# Frost5000Beta_Sch.net
KiCad netlist of a schematic drawn in Altium Designer
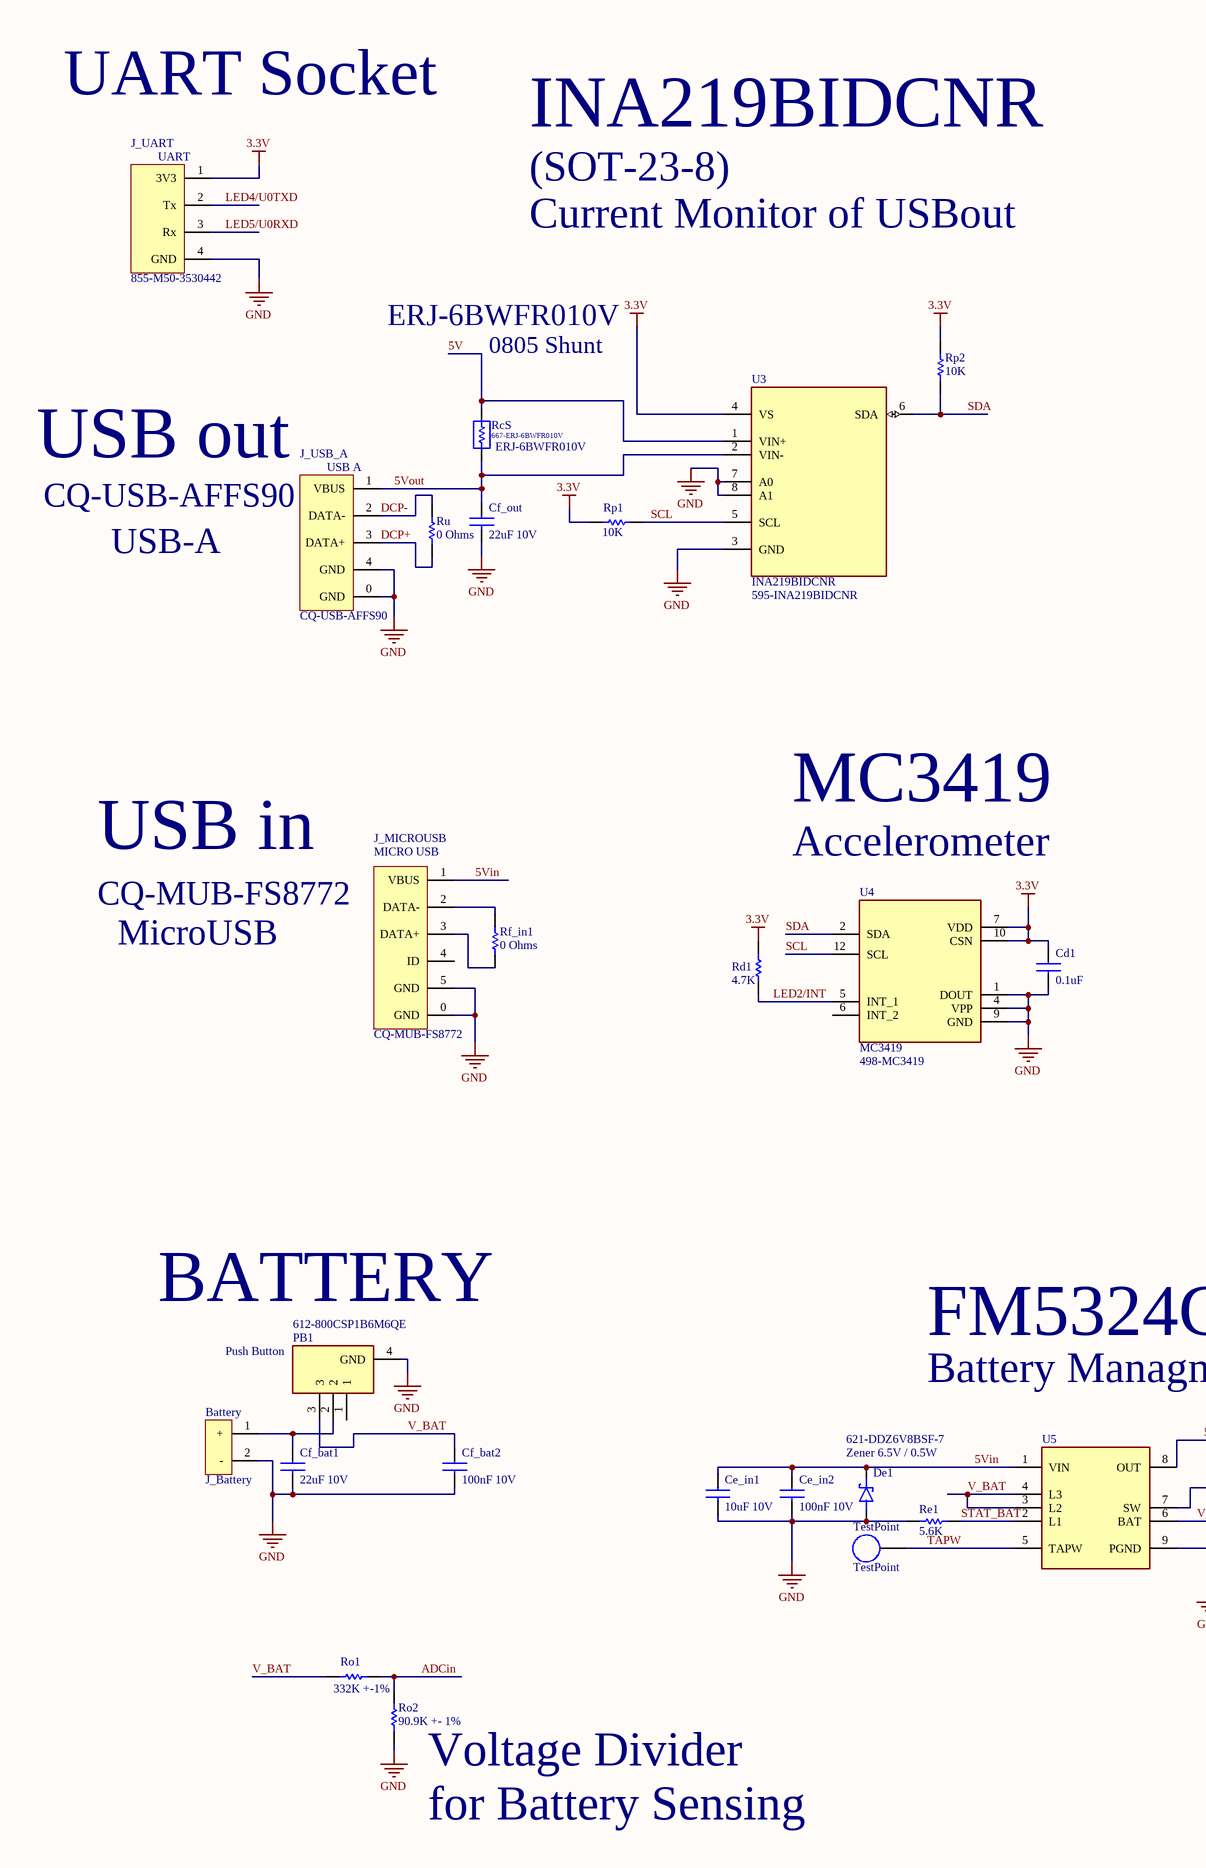
[diagram p0: Frost5000Beta_Sch.SchDoc, left]
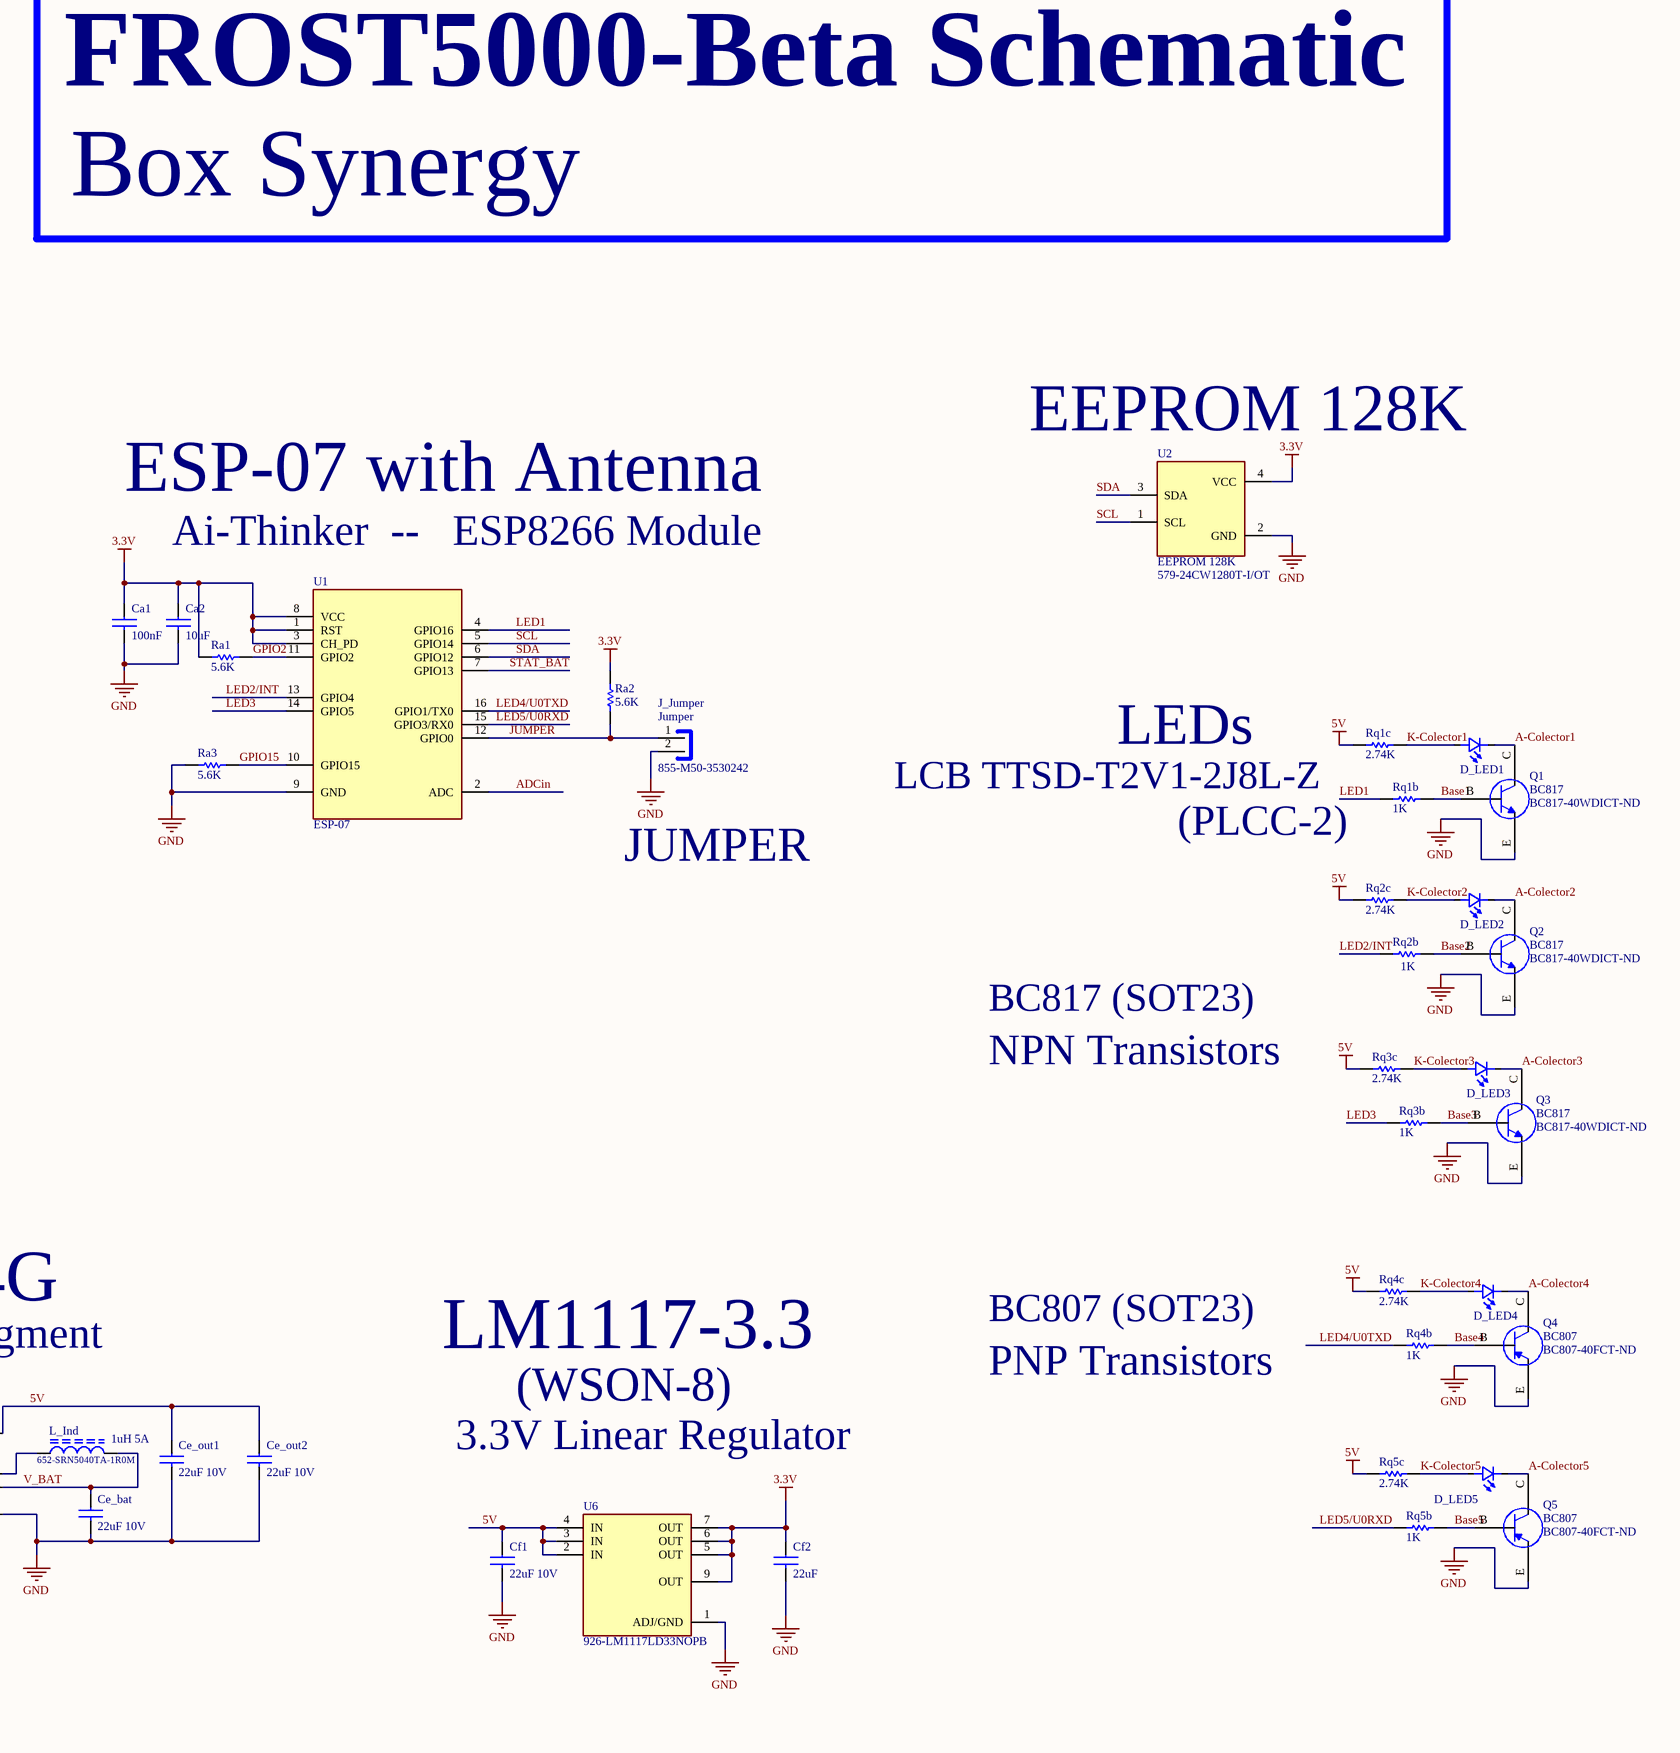
[diagram p1: Frost5000Beta_Sch.SchDoc, right]

(export (version "E")
  (design (tool "Eeschema 10.0.6"))
  (components
    (comp (ref "Ca1")
      (value "100nF")
      (footprint "CAP_0603")
      (description "Capac Ceramic SMD 0603")
      (libsource (lib "Frost5000Beta_LIB_Pasivos_Sch") (part "Cap_0603_Ceramic"))
    )
    (comp (ref "Ca2")
      (value "10uF")
      (footprint "CAP_1206")
      (description "Capac Ceramic SMD")
      (libsource (lib "Frost5000Beta_LIB_Pasivos_Sch") (part "Cap_1206_Ceramic"))
    )
    (comp (ref "Cd1")
      (value "0.1uF")
      (footprint "CAP_0603")
      (description "Capac Ceramic SMD 0603")
      (libsource (lib "Frost5000Beta_LIB_Pasivos_Sch") (part "Cap_0603_Ceramic"))
    )
    (comp (ref "Ce_bat")
      (value "22uF 10V")
      (footprint "CAP_1206")
      (description "Capac Ceramic SMD")
      (libsource (lib "Frost5000Beta_LIB_Pasivos_Sch") (part "Cap_1206_Ceramic"))
    )
    (comp (ref "Ce_in1")
      (value "10uF 10V")
      (footprint "CAP_1206")
      (description "Capac Ceramic SMD")
      (libsource (lib "Frost5000Beta_LIB_Pasivos_Sch") (part "Cap_1206_Ceramic"))
    )
    (comp (ref "Ce_in2")
      (value "100nF 10V")
      (footprint "CAP_0603")
      (description "Capac Ceramic SMD 0603")
      (libsource (lib "Frost5000Beta_LIB_Pasivos_Sch") (part "Cap_0603_Ceramic"))
    )
    (comp (ref "Ce_out1")
      (value "22uF 10V")
      (footprint "CAP_1210")
      (description "Capac Ceramic SMD 1210")
      (libsource (lib "Frost5000Beta_LIB_Pasivos_Sch") (part "Cap_1210_Ceramic"))
    )
    (comp (ref "Ce_out2")
      (value "22uF 10V")
      (footprint "CAP_1206")
      (description "Capac Ceramic SMD")
      (libsource (lib "Frost5000Beta_LIB_Pasivos_Sch") (part "Cap_1206_Ceramic"))
    )
    (comp (ref "Cf1")
      (value "22uF 10V")
      (footprint "CAP_0603")
      (description "Capac Ceramic SMD 0603")
      (libsource (lib "Frost5000Beta_LIB_Pasivos_Sch") (part "Cap_0603_Ceramic"))
    )
    (comp (ref "Cf2")
      (value "22uF")
      (footprint "CAP_0603")
      (description "Capac Ceramic SMD 0603")
      (libsource (lib "Frost5000Beta_LIB_Pasivos_Sch") (part "Cap_0603_Ceramic"))
    )
    (comp (ref "Cf_bat1")
      (value "22uF 10V")
      (footprint "CAP_1206")
      (description "Capac Ceramic SMD")
      (libsource (lib "Frost5000Beta_LIB_Pasivos_Sch") (part "Cap_1206_Ceramic"))
    )
    (comp (ref "Cf_bat2")
      (value "100nF 10V")
      (footprint "CAP_0603")
      (description "Capac Ceramic SMD 0603")
      (libsource (lib "Frost5000Beta_LIB_Pasivos_Sch") (part "Cap_0603_Ceramic"))
    )
    (comp (ref "Cf_out")
      (value "22uF 10V")
      (footprint "CAP_1210")
      (description "Capac Ceramic SMD 1210")
      (libsource (lib "Frost5000Beta_LIB_Pasivos_Sch") (part "Cap_1210_Ceramic"))
    )
    (comp (ref "De1")
      (value "Zener 6.5V / 0.5W")
      (footprint "Zener-SOD323F")
      (fields
        (field (name "MF") "Littelfuse")
        (field (name "MP") "SMF5.0AT1G")
        (field (name "SUPPLIER PART NUMBER 1") "621-DDZ6V8BSF-7")
      )
      (libsource (lib "Frost5000Beta_LIB_Otros_Sch") (part "Zener"))
    )
    (comp (ref "D_LED1")
      (value "LCB TTSD-T2V1-2J8L-Z")
      (footprint "LED_PLCC-2")
      (description "Blue LED PLCC-2")
      (fields (field (name "MF") "Broadcom Limited") (field (name "MP") "HSMW-C191"))
      (libsource (lib "Frost5000Beta_LIB_Otros_Sch") (part "LCB_TTSD"))
    )
    (comp (ref "D_LED2")
      (value "LCB TTSD-T2V1-2J8L-Z")
      (footprint "LED_PLCC-2")
      (description "Blue LED PLCC-2")
      (fields (field (name "MF") "Broadcom Limited") (field (name "MP") "HSMW-C191"))
      (libsource (lib "Frost5000Beta_LIB_Otros_Sch") (part "LCB_TTSD"))
    )
    (comp (ref "D_LED3")
      (value "LCB TTSD-T2V1-2J8L-Z")
      (footprint "LED_PLCC-2")
      (description "Blue LED PLCC-2")
      (fields (field (name "MF") "Broadcom Limited") (field (name "MP") "HSMW-C191"))
      (libsource (lib "Frost5000Beta_LIB_Otros_Sch") (part "LCB_TTSD"))
    )
    (comp (ref "D_LED4")
      (value "LCB TTSD-T2V1-2J8L-Z")
      (footprint "LED_PLCC-2")
      (description "Blue LED PLCC-2")
      (fields (field (name "MF") "Broadcom Limited") (field (name "MP") "HSMW-C191"))
      (libsource (lib "Frost5000Beta_LIB_Otros_Sch") (part "LCB_TTSD"))
    )
    (comp (ref "D_LED5")
      (value "LCB TTSD-T2V1-2J8L-Z")
      (footprint "LED_PLCC-2")
      (description "Blue LED PLCC-2")
      (fields (field (name "MF") "Broadcom Limited") (field (name "MP") "HSMW-C191"))
      (libsource (lib "Frost5000Beta_LIB_Otros_Sch") (part "LCB_TTSD"))
    )
    (comp (ref "J_Battery")
      (value "Connx2_Battery")
      (footprint "Battery")
      (description "NO SOCKET")
      (libsource (lib "Frost5000Beta_LIB_Conectores_Sch") (part "Connx2_Battery"))
    )
    (comp (ref "J_Jumper")
      (value "M50-3530242")
      (footprint "JUMPER-1.27 mm")
      (description "1.27mm Pin Header 2x1")
      (fields (field (name "SUPPLIER PART NUMBER 1") "855-M50-3530242"))
      (libsource (lib "Summits7Beta_LIB_Conectores_Sch") (part "Jumper"))
    )
    (comp (ref "J_MICROUSB")
      (value "CQ-MUB-FS8772")
      (footprint "MICRO USB")
      (description "MicroUSB B-type Socket")
      (libsource (lib "Frost5000Beta_LIB_Conectores_Sch") (part "MicroUSB"))
    )
    (comp (ref "J_UART")
      (value "M50-3530442")
      (footprint "UART-1.27mm")
      (description "1.27mm Pin Header 4x1")
      (fields (field (name "SUPPLIER PART NUMBER 1") "855-M50-3530442"))
      (libsource (lib "Summits7Beta_LIB_Conectores_Sch") (part "Connx4_UART"))
    )
    (comp (ref "J_USB_A")
      (value "CQ-USB-AFFS90")
      (footprint "USB-A__IPX8")
      (description "USB-A Socket")
      (libsource (lib "Frost5000Beta_LIB_Conectores_Sch") (part "USB-A 5V"))
    )
    (comp (ref "L_Ind")
      (value "1uH 5A")
      (footprint "Inductor_SRN5040")
      (description "Inductor_SRN5040")
      (fields (field (name "MF") "Vishay Dale") (field (name "SUPPLIER PART NUMBER 1") "652-SRN5040TA-1R0M"))
      (libsource (lib "Frost5000Beta_LIB_Pasivos_Sch") (part "Ind_SRN5040"))
    )
    (comp (ref "PB1")
      (value "Push Button")
      (footprint "800C Switch")
      (description "Push Button 800C")
      (fields (field (name "SUPPLIER PART NUMBER 1") "612-800CSP1B6M6QE"))
      (libsource (lib "Frost5000Beta_LIB_Otros_Sch") (part "800C"))
    )
    (comp (ref "Q1")
      (value "BC817")
      (footprint "Transistor_SOT23-3")
      (description "Transistor NPN")
      (fields (field (name "SUPPLIER PART NUMBER 1") "BC817-40WDICT-ND"))
      (libsource (lib "Frost5000Beta_LIB_Integrados_Sch") (part "BC817"))
    )
    (comp (ref "Q2")
      (value "BC817")
      (footprint "Transistor_SOT23-3")
      (description "Transistor NPN")
      (fields (field (name "SUPPLIER PART NUMBER 1") "BC817-40WDICT-ND"))
      (libsource (lib "Frost5000Beta_LIB_Integrados_Sch") (part "BC817"))
    )
    (comp (ref "Q3")
      (value "BC817")
      (footprint "Transistor_SOT23-3")
      (description "Transistor NPN")
      (fields (field (name "SUPPLIER PART NUMBER 1") "BC817-40WDICT-ND"))
      (libsource (lib "Frost5000Beta_LIB_Integrados_Sch") (part "BC817"))
    )
    (comp (ref "Q4")
      (value "BC807")
      (footprint "Transistor_SOT23-3")
      (description "Transistor PNP")
      (fields (field (name "SUPPLIER PART NUMBER 1") "BC807-40FCT-ND"))
      (libsource (lib "Frost5000Beta_LIB_Integrados_Sch") (part "BC807"))
    )
    (comp (ref "Q5")
      (value "BC807")
      (footprint "Transistor_SOT23-3")
      (description "Transistor PNP")
      (fields (field (name "SUPPLIER PART NUMBER 1") "BC807-40FCT-ND"))
      (libsource (lib "Frost5000Beta_LIB_Integrados_Sch") (part "BC807"))
    )
    (comp (ref "Ra1")
      (value "5.6K")
      (footprint "RES_0603")
      (description "Resistor SMD")
      (fields (field (name "PUBLISHER") "Altium Limited"))
      (libsource (lib "Frost5000Beta_LIB_Pasivos_Sch") (part "Res_0603"))
    )
    (comp (ref "Ra2")
      (value "5.6K")
      (footprint "RES_0603")
      (description "Resistor SMD")
      (fields (field (name "PUBLISHER") "Altium Limited"))
      (libsource (lib "Frost5000Beta_LIB_Pasivos_Sch") (part "Res_0603"))
    )
    (comp (ref "Ra3")
      (value "5.6K")
      (footprint "RES_0603")
      (description "Resistor SMD")
      (fields (field (name "PUBLISHER") "Altium Limited"))
      (libsource (lib "Frost5000Beta_LIB_Pasivos_Sch") (part "Res_0603"))
    )
    (comp (ref "RcS")
      (value "ERJ-6BWFR010V")
      (footprint "RES-SHUNT-0805")
      (description "Shunt 0.01 Ohm 0.5W 1% SMD Resistor")
      (fields
        (field (name "SUPPLIER PART NUMBER 1") "667-ERJ-6BWFR010V")
        (field (name "PUBLISHER") "Altium Limited")
      )
      (libsource (lib "Frost5000Beta_LIB_Pasivos_Sch") (part "Shunt_0805"))
    )
    (comp (ref "Rd1")
      (value "4.7K")
      (footprint "RES_0603")
      (description "Resistor SMD")
      (fields (field (name "PUBLISHER") "Altium Limited"))
      (libsource (lib "Frost5000Beta_LIB_Pasivos_Sch") (part "Res_0603"))
    )
    (comp (ref "Re1")
      (value "5.6K")
      (footprint "RES_0603")
      (description "Resistor SMD")
      (fields (field (name "PUBLISHER") "Altium Limited"))
      (libsource (lib "Frost5000Beta_LIB_Pasivos_Sch") (part "Res_0603"))
    )
    (comp (ref "Rf_in1")
      (value "0 Ohms")
      (footprint "RES_0603")
      (description "Resistor SMD")
      (fields (field (name "PUBLISHER") "Altium Limited"))
      (libsource (lib "Frost5000Beta_LIB_Pasivos_Sch") (part "Res_0603"))
    )
    (comp (ref "Ro1")
      (value "332K +-1%")
      (footprint "RES_0603")
      (description "Resistor SMD")
      (fields (field (name "PUBLISHER") "Altium Limited"))
      (libsource (lib "Frost5000Beta_LIB_Pasivos_Sch") (part "Res_0603"))
    )
    (comp (ref "Ro2")
      (value "90.9K +- 1%")
      (footprint "RES_0603")
      (description "Resistor SMD")
      (fields (field (name "PUBLISHER") "Altium Limited"))
      (libsource (lib "Frost5000Beta_LIB_Pasivos_Sch") (part "Res_0603"))
    )
    (comp (ref "Rp1")
      (value "10K")
      (footprint "RES_0603")
      (description "Resistor SMD")
      (fields (field (name "PUBLISHER") "Altium Limited"))
      (libsource (lib "Frost5000Beta_LIB_Pasivos_Sch") (part "Res_0603"))
    )
    (comp (ref "Rp2")
      (value "10K")
      (footprint "RES_0603")
      (description "Resistor SMD")
      (fields (field (name "PUBLISHER") "Altium Limited"))
      (libsource (lib "Frost5000Beta_LIB_Pasivos_Sch") (part "Res_0603"))
    )
    (comp (ref "Rq1b")
      (value "1K")
      (footprint "RES_0603")
      (description "Resistor SMD")
      (fields (field (name "PUBLISHER") "Altium Limited"))
      (libsource (lib "Frost5000Beta_LIB_Pasivos_Sch") (part "Res_0603"))
    )
    (comp (ref "Rq1c")
      (value "2.74K")
      (footprint "RES_0603")
      (description "Resistor SMD")
      (fields (field (name "PUBLISHER") "Altium Limited"))
      (libsource (lib "Frost5000Beta_LIB_Pasivos_Sch") (part "Res_0603"))
    )
    (comp (ref "Rq2b")
      (value "1K")
      (footprint "RES_0603")
      (description "Resistor SMD")
      (fields (field (name "PUBLISHER") "Altium Limited"))
      (libsource (lib "Frost5000Beta_LIB_Pasivos_Sch") (part "Res_0603"))
    )
    (comp (ref "Rq2c")
      (value "2.74K")
      (footprint "RES_0603")
      (description "Resistor SMD")
      (fields (field (name "PUBLISHER") "Altium Limited"))
      (libsource (lib "Frost5000Beta_LIB_Pasivos_Sch") (part "Res_0603"))
    )
    (comp (ref "Rq3b")
      (value "1K")
      (footprint "RES_0603")
      (description "Resistor SMD")
      (fields (field (name "PUBLISHER") "Altium Limited"))
      (libsource (lib "Frost5000Beta_LIB_Pasivos_Sch") (part "Res_0603"))
    )
    (comp (ref "Rq3c")
      (value "2.74K")
      (footprint "RES_0603")
      (description "Resistor SMD")
      (fields (field (name "PUBLISHER") "Altium Limited"))
      (libsource (lib "Frost5000Beta_LIB_Pasivos_Sch") (part "Res_0603"))
    )
    (comp (ref "Rq4b")
      (value "1K")
      (footprint "RES_0603")
      (description "Resistor SMD")
      (fields (field (name "PUBLISHER") "Altium Limited"))
      (libsource (lib "Frost5000Beta_LIB_Pasivos_Sch") (part "Res_0603"))
    )
    (comp (ref "Rq4c")
      (value "2.74K")
      (footprint "RES_0603")
      (description "Resistor SMD")
      (fields (field (name "PUBLISHER") "Altium Limited"))
      (libsource (lib "Frost5000Beta_LIB_Pasivos_Sch") (part "Res_0603"))
    )
    (comp (ref "Rq5b")
      (value "1K")
      (footprint "RES_0603")
      (description "Resistor SMD")
      (fields (field (name "PUBLISHER") "Altium Limited"))
      (libsource (lib "Frost5000Beta_LIB_Pasivos_Sch") (part "Res_0603"))
    )
    (comp (ref "Rq5c")
      (value "2.74K")
      (footprint "RES_0603")
      (description "Resistor SMD")
      (fields (field (name "PUBLISHER") "Altium Limited"))
      (libsource (lib "Frost5000Beta_LIB_Pasivos_Sch") (part "Res_0603"))
    )
    (comp (ref "Ru")
      (value "0 Ohms")
      (footprint "RES_0603")
      (description "Resistor SMD")
      (fields (field (name "PUBLISHER") "Altium Limited"))
      (libsource (lib "Frost5000Beta_LIB_Pasivos_Sch") (part "Res_0603"))
    )
    (comp (ref "TestPoint")
      (value "TestPoint")
      (footprint "TestPoint")
      (libsource (lib "Frost5000Beta_LIB_Otros_Sch") (part "TestPoint"))
    )
    (comp (ref "U1")
      (value "ESP-07")
      (footprint "ESP-07")
      (description "ESP07 Module with Antenna Ai-Thinker")
      (fields (field (name "MP") "AP65111AWU-7") (field (name "MF") "Diodes Inc."))
      (libsource (lib "Frost5000Beta_LIB_Integrados_Sch") (part "ESP-07"))
    )
    (comp (ref "U2")
      (value "EEPROM 128K")
      (footprint "24CW128")
      (fields (field (name "SUPPLIER PART NUMBER 1") "579-24CW1280T-I/OT"))
      (libsource (lib "Frost5000Beta_LIB_Integrados_Sch") (part "24CW1280T-I/OT"))
    )
    (comp (ref "U3")
      (value "INA219BIDCNR")
      (footprint "INA219B SOT23")
      (description "Current Monitor Regulator High-Side 10mA SOT-23-8")
      (fields
        (field (name "DIGI-KEY_PART_NUMBER") "296-46420-1-ND")
        (field (name "MF") "Texas Instruments")
        (field (name "SUPPLIER PART NUMBER 1") "595-INA219BIDCNR")
      )
      (libsource (lib "Frost5000Beta_LIB_Integrados_Sch") (part "INA219BIDCNR"))
    )
    (comp (ref "U4")
      (value "MC3419")
      (footprint "MC3419")
      (description "Accelerometer")
      (fields
        (field (name "MP") "LSM303AGR")
        (field (name "MF") "STMicroelectronics")
        (field (name "SUPPLIER PART NUMBER 1") "498-MC3419")
      )
      (libsource (lib "Frost5000Beta_LIB_Integrados_Sch") (part "MC3419"))
    )
    (comp (ref "U5")
      (value "FM5324G")
      (footprint "SOP8")
      (description "Power Battery Management IC")
      (fields (field (name "MP") "LT1117IST-5#PBF") (field (name "MF") "Analog Devices"))
      (libsource (lib "Frost5000Beta_LIB_Integrados_Sch") (part "FM5324G"))
    )
    (comp (ref "U6")
      (value "LM1117LD-3.3/NOPB")
      (footprint "LM1117-3.3-WSON-8")
      (description "LDO Regulator Pos 3.3V 0.8A Texas - WSON8")
      (fields
        (field (name "MP") "LT1117IST-5#PBF")
        (field (name "MF") "Analog Devices")
        (field (name "SUPPLIER PART NUMBER 1") "926-LM1117LD33NOPB")
      )
      (libsource (lib "Frost5000Beta_LIB_Integrados_Sch") (part "LM1117LD-3.3/NOPB"))
    )
  )
  (nets
    (net (code "1") (name "/5Vin") (class "Default")
      (node (ref "Ce_in1") (pin "1") (pinfunction "1_1") (pintype "passive"))
      (node (ref "Ce_in2") (pin "1") (pinfunction "1_1") (pintype "passive"))
      (node (ref "De1") (pin "C") (pinfunction "C_C") (pintype "passive"))
      (node (ref "J_MICROUSB") (pin "1") (pinfunction "VBUS_1") (pintype "power_in"))
      (node (ref "U5") (pin "1") (pinfunction "VIN_1") (pintype "passive"))
    )
    (net (code "2") (name "/5Vout") (class "Default")
      (node (ref "Cf_out") (pin "1") (pinfunction "1_1") (pintype "passive"))
      (node (ref "J_USB_A") (pin "1") (pinfunction "VBUS_1") (pintype "power_in"))
      (node (ref "RcS") (pin "1") (pinfunction "1_1") (pintype "passive"))
      (node (ref "U3") (pin "2") (pinfunction "VIN-_2") (pintype "passive"))
    )
    (net (code "3") (name "/A-Colector1") (class "Default")
      (node (ref "D_LED1") (pin "1") (pinfunction "K_1") (pintype "passive"))
      (node (ref "Q1") (pin "C") (pinfunction "C_C") (pintype "passive"))
    )
    (net (code "4") (name "/A-Colector2") (class "Default")
      (node (ref "D_LED2") (pin "1") (pinfunction "K_1") (pintype "passive"))
      (node (ref "Q2") (pin "C") (pinfunction "C_C") (pintype "passive"))
    )
    (net (code "5") (name "/A-Colector3") (class "Default")
      (node (ref "D_LED3") (pin "1") (pinfunction "K_1") (pintype "passive"))
      (node (ref "Q3") (pin "C") (pinfunction "C_C") (pintype "passive"))
    )
    (net (code "6") (name "/A-Colector4") (class "Default")
      (node (ref "D_LED4") (pin "1") (pinfunction "K_1") (pintype "passive"))
      (node (ref "Q4") (pin "C") (pinfunction "C_C") (pintype "passive"))
    )
    (net (code "7") (name "/A-Colector5") (class "Default")
      (node (ref "D_LED5") (pin "1") (pinfunction "K_1") (pintype "passive"))
      (node (ref "Q5") (pin "C") (pinfunction "C_C") (pintype "passive"))
    )
    (net (code "8") (name "/ADCin") (class "Default")
      (node (ref "Ro1") (pin "2") (pinfunction "2_2") (pintype "passive"))
      (node (ref "Ro2") (pin "2") (pinfunction "2_2") (pintype "passive"))
      (node (ref "U1") (pin "2") (pinfunction "ADC_2") (pintype "passive"))
    )
    (net (code "9") (name "/Base1") (class "Default")
      (node (ref "Q1") (pin "B") (pinfunction "B_B") (pintype "passive"))
      (node (ref "Rq1b") (pin "1") (pinfunction "1_1") (pintype "passive"))
    )
    (net (code "10") (name "/Base2") (class "Default")
      (node (ref "Q2") (pin "B") (pinfunction "B_B") (pintype "passive"))
      (node (ref "Rq2b") (pin "1") (pinfunction "1_1") (pintype "passive"))
    )
    (net (code "11") (name "/Base3") (class "Default")
      (node (ref "Q3") (pin "B") (pinfunction "B_B") (pintype "passive"))
      (node (ref "Rq3b") (pin "1") (pinfunction "1_1") (pintype "passive"))
    )
    (net (code "12") (name "/Base4") (class "Default")
      (node (ref "Q4") (pin "B") (pinfunction "B_B") (pintype "passive"))
      (node (ref "Rq4b") (pin "1") (pinfunction "1_1") (pintype "passive"))
    )
    (net (code "13") (name "/Base5") (class "Default")
      (node (ref "Q5") (pin "B") (pinfunction "B_B") (pintype "passive"))
      (node (ref "Rq5b") (pin "1") (pinfunction "1_1") (pintype "passive"))
    )
    (net (code "14") (name "/DCP+") (class "Default")
      (node (ref "J_USB_A") (pin "3") (pinfunction "DATA+_3") (pintype "passive"))
      (node (ref "Ru") (pin "1") (pinfunction "1_1") (pintype "passive"))
    )
    (net (code "15") (name "/DCP-") (class "Default")
      (node (ref "J_USB_A") (pin "2") (pinfunction "DATA-_2") (pintype "passive"))
      (node (ref "Ru") (pin "2") (pinfunction "2_2") (pintype "passive"))
    )
    (net (code "16") (name "/GPIO2") (class "Default")
      (node (ref "Ra1") (pin "1") (pinfunction "1_1") (pintype "passive"))
      (node (ref "U1") (pin "11") (pinfunction "GPIO2_11") (pintype "passive"))
    )
    (net (code "17") (name "/GPIO15") (class "Default")
      (node (ref "Ra3") (pin "1") (pinfunction "1_1") (pintype "passive"))
      (node (ref "U1") (pin "10") (pinfunction "GPIO15_10") (pintype "passive"))
    )
    (net (code "18") (name "/JUMPER") (class "Default")
      (node (ref "J_Jumper") (pin "1") (pinfunction "1_1") (pintype "passive"))
      (node (ref "Ra2") (pin "1") (pinfunction "1_1") (pintype "passive"))
      (node (ref "U1") (pin "12") (pinfunction "GPIO0_12") (pintype "passive"))
    )
    (net (code "19") (name "/K-Colector1") (class "Default")
      (node (ref "D_LED1") (pin "2") (pinfunction "A_2") (pintype "passive"))
      (node (ref "Rq1c") (pin "1") (pinfunction "1_1") (pintype "passive"))
    )
    (net (code "20") (name "/K-Colector2") (class "Default")
      (node (ref "D_LED2") (pin "2") (pinfunction "A_2") (pintype "passive"))
      (node (ref "Rq2c") (pin "1") (pinfunction "1_1") (pintype "passive"))
    )
    (net (code "21") (name "/K-Colector3") (class "Default")
      (node (ref "D_LED3") (pin "2") (pinfunction "A_2") (pintype "passive"))
      (node (ref "Rq3c") (pin "1") (pinfunction "1_1") (pintype "passive"))
    )
    (net (code "22") (name "/K-Colector4") (class "Default")
      (node (ref "D_LED4") (pin "2") (pinfunction "A_2") (pintype "passive"))
      (node (ref "Rq4c") (pin "1") (pinfunction "1_1") (pintype "passive"))
    )
    (net (code "23") (name "/K-Colector5") (class "Default")
      (node (ref "D_LED5") (pin "2") (pinfunction "A_2") (pintype "passive"))
      (node (ref "Rq5c") (pin "1") (pinfunction "1_1") (pintype "passive"))
    )
    (net (code "24") (name "/LED1") (class "Default")
      (node (ref "Rq1b") (pin "2") (pinfunction "2_2") (pintype "passive"))
      (node (ref "U1") (pin "4") (pinfunction "GPIO16_4") (pintype "passive"))
    )
    (net (code "25") (name "/LED2{slash}INT") (class "Default")
      (node (ref "Rd1") (pin "2") (pinfunction "2_2") (pintype "passive"))
      (node (ref "Rq2b") (pin "2") (pinfunction "2_2") (pintype "passive"))
      (node (ref "U1") (pin "13") (pinfunction "GPIO4_13") (pintype "passive"))
      (node (ref "U4") (pin "5") (pinfunction "INT_1_5") (pintype "passive"))
    )
    (net (code "26") (name "/LED3") (class "Default")
      (node (ref "Rq3b") (pin "2") (pinfunction "2_2") (pintype "passive"))
      (node (ref "U1") (pin "14") (pinfunction "GPIO5_14") (pintype "passive"))
    )
    (net (code "27") (name "/LED4{slash}U0TXD") (class "Default")
      (node (ref "J_UART") (pin "2") (pinfunction "Tx_2") (pintype "passive"))
      (node (ref "Rq4b") (pin "2") (pinfunction "2_2") (pintype "passive"))
      (node (ref "U1") (pin "16") (pinfunction "GPIO1/TX0_16") (pintype "passive"))
    )
    (net (code "28") (name "/LED5{slash}U0RXD") (class "Default")
      (node (ref "J_UART") (pin "3") (pinfunction "Rx_3") (pintype "passive"))
      (node (ref "Rq5b") (pin "2") (pinfunction "2_2") (pintype "passive"))
      (node (ref "U1") (pin "15") (pinfunction "GPIO3/RX0_15") (pintype "passive"))
    )
    (net (code "29") (name "/SCL") (class "Default")
      (node (ref "Rp1") (pin "2") (pinfunction "2_2") (pintype "passive"))
      (node (ref "U1") (pin "5") (pinfunction "GPIO14_5") (pintype "passive"))
      (node (ref "U2") (pin "1") (pinfunction "SCL_1") (pintype "passive"))
      (node (ref "U3") (pin "5") (pinfunction "SCL_5") (pintype "passive"))
      (node (ref "U4") (pin "12") (pinfunction "SCL_12") (pintype "passive"))
    )
    (net (code "30") (name "/SDA") (class "Default")
      (node (ref "Rp2") (pin "2") (pinfunction "2_2") (pintype "passive"))
      (node (ref "U1") (pin "6") (pinfunction "GPIO12_6") (pintype "passive"))
      (node (ref "U2") (pin "3") (pinfunction "SDA_3") (pintype "passive"))
      (node (ref "U3") (pin "6") (pinfunction "SDA_6") (pintype "bidirectional"))
      (node (ref "U4") (pin "2") (pinfunction "SDA_2") (pintype "passive"))
    )
    (net (code "31") (name "/STAT_BAT") (class "Default")
      (node (ref "Re1") (pin "1") (pinfunction "1_1") (pintype "passive"))
      (node (ref "U1") (pin "7") (pinfunction "GPIO13_7") (pintype "passive"))
      (node (ref "U5") (pin "2") (pinfunction "L1_2") (pintype "passive"))
    )
    (net (code "32") (name "/TAPW") (class "Default")
      (node (ref "TestPoint") (pin "1") (pinfunction "1_1") (pintype "passive"))
      (node (ref "U5") (pin "5") (pinfunction "TAPW_5") (pintype "passive"))
    )
    (net (code "33") (name "/V_BAT") (class "Default")
      (node (ref "Ce_bat") (pin "1") (pinfunction "1_1") (pintype "passive"))
      (node (ref "Cf_bat2") (pin "1") (pinfunction "1_1") (pintype "passive"))
      (node (ref "L_Ind") (pin "1") (pinfunction "1_1") (pintype "passive"))
      (node (ref "PB1") (pin "3") (pinfunction "3_3") (pintype "passive"))
      (node (ref "Ro1") (pin "1") (pinfunction "1_1") (pintype "passive"))
      (node (ref "U5") (pin "3") (pinfunction "L2_3") (pintype "passive"))
      (node (ref "U5") (pin "4") (pinfunction "L3_4") (pintype "passive"))
      (node (ref "U5") (pin "6") (pinfunction "BAT_6") (pintype "passive"))
    )
    (net (code "34") (name "3.3V") (class "Default")
      (node (ref "Ca1") (pin "1") (pinfunction "1_1") (pintype "passive"))
      (node (ref "Ca2") (pin "1") (pinfunction "1_1") (pintype "passive"))
      (node (ref "Cd1") (pin "1") (pinfunction "1_1") (pintype "passive"))
      (node (ref "Cf2") (pin "1") (pinfunction "1_1") (pintype "passive"))
      (node (ref "J_UART") (pin "1") (pinfunction "3V3_1") (pintype "passive"))
      (node (ref "Ra1") (pin "2") (pinfunction "2_2") (pintype "passive"))
      (node (ref "Ra2") (pin "2") (pinfunction "2_2") (pintype "passive"))
      (node (ref "Rd1") (pin "1") (pinfunction "1_1") (pintype "passive"))
      (node (ref "Rp1") (pin "1") (pinfunction "1_1") (pintype "passive"))
      (node (ref "Rp2") (pin "1") (pinfunction "1_1") (pintype "passive"))
      (node (ref "U1") (pin "1") (pinfunction "RST_1") (pintype "passive"))
      (node (ref "U1") (pin "3") (pinfunction "CH_PD_3") (pintype "passive"))
      (node (ref "U1") (pin "8") (pinfunction "VCC_8") (pintype "passive"))
      (node (ref "U2") (pin "4") (pinfunction "VCC_4") (pintype "passive"))
      (node (ref "U3") (pin "4") (pinfunction "VS_4") (pintype "power_in"))
      (node (ref "U4") (pin "10") (pinfunction "CSN_10") (pintype "passive"))
      (node (ref "U4") (pin "7") (pinfunction "VDD_7") (pintype "passive"))
      (node (ref "U6") (pin "5") (pinfunction "OUT_5") (pintype "passive"))
      (node (ref "U6") (pin "6") (pinfunction "OUT_6") (pintype "passive"))
      (node (ref "U6") (pin "7") (pinfunction "OUT_7") (pintype "passive"))
      (node (ref "U6") (pin "9") (pinfunction "OUT_9") (pintype "passive"))
    )
    (net (code "35") (name "5V") (class "Default")
      (node (ref "Ce_out1") (pin "1") (pinfunction "1_1") (pintype "passive"))
      (node (ref "Ce_out2") (pin "1") (pinfunction "1_1") (pintype "passive"))
      (node (ref "Cf1") (pin "1") (pinfunction "1_1") (pintype "passive"))
      (node (ref "RcS") (pin "2") (pinfunction "2_2") (pintype "passive"))
      (node (ref "Rq1c") (pin "2") (pinfunction "2_2") (pintype "passive"))
      (node (ref "Rq2c") (pin "2") (pinfunction "2_2") (pintype "passive"))
      (node (ref "Rq3c") (pin "2") (pinfunction "2_2") (pintype "passive"))
      (node (ref "Rq4c") (pin "2") (pinfunction "2_2") (pintype "passive"))
      (node (ref "Rq5c") (pin "2") (pinfunction "2_2") (pintype "passive"))
      (node (ref "U3") (pin "1") (pinfunction "VIN+_1") (pintype "passive"))
      (node (ref "U5") (pin "8") (pinfunction "OUT_8") (pintype "passive"))
      (node (ref "U6") (pin "2") (pinfunction "IN_2") (pintype "passive"))
      (node (ref "U6") (pin "3") (pinfunction "IN_3") (pintype "passive"))
      (node (ref "U6") (pin "4") (pinfunction "IN_4") (pintype "passive"))
    )
    (net (code "36") (name "GND") (class "Default")
      (node (ref "Ca1") (pin "2") (pinfunction "2_2") (pintype "passive"))
      (node (ref "Ca2") (pin "2") (pinfunction "2_2") (pintype "passive"))
      (node (ref "Cd1") (pin "2") (pinfunction "2_2") (pintype "passive"))
      (node (ref "Ce_bat") (pin "2") (pinfunction "2_2") (pintype "passive"))
      (node (ref "Ce_in1") (pin "2") (pinfunction "2_2") (pintype "passive"))
      (node (ref "Ce_in2") (pin "2") (pinfunction "2_2") (pintype "passive"))
      (node (ref "Ce_out1") (pin "2") (pinfunction "2_2") (pintype "passive"))
      (node (ref "Ce_out2") (pin "2") (pinfunction "2_2") (pintype "passive"))
      (node (ref "Cf1") (pin "2") (pinfunction "2_2") (pintype "passive"))
      (node (ref "Cf2") (pin "2") (pinfunction "2_2") (pintype "passive"))
      (node (ref "Cf_bat1") (pin "2") (pinfunction "2_2") (pintype "passive"))
      (node (ref "Cf_bat2") (pin "2") (pinfunction "2_2") (pintype "passive"))
      (node (ref "Cf_out") (pin "2") (pinfunction "2_2") (pintype "passive"))
      (node (ref "De1") (pin "A") (pinfunction "A_A") (pintype "passive"))
      (node (ref "J_Battery") (pin "2") (pinfunction "-_2") (pintype "passive"))
      (node (ref "J_Jumper") (pin "2") (pinfunction "2_2") (pintype "passive"))
      (node (ref "J_MICROUSB") (pin "0") (pinfunction "GND_0") (pintype "passive"))
      (node (ref "J_MICROUSB") (pin "5") (pinfunction "GND_5") (pintype "passive"))
      (node (ref "J_UART") (pin "4") (pinfunction "GND_4") (pintype "passive"))
      (node (ref "J_USB_A") (pin "0") (pinfunction "GND_0") (pintype "passive"))
      (node (ref "J_USB_A") (pin "4") (pinfunction "GND_4") (pintype "passive"))
      (node (ref "PB1") (pin "4") (pinfunction "GND_4") (pintype "passive"))
      (node (ref "Q1") (pin "E") (pinfunction "E_E") (pintype "passive"))
      (node (ref "Q2") (pin "E") (pinfunction "E_E") (pintype "passive"))
      (node (ref "Q3") (pin "E") (pinfunction "E_E") (pintype "passive"))
      (node (ref "Q4") (pin "E") (pinfunction "E_E") (pintype "passive"))
      (node (ref "Q5") (pin "E") (pinfunction "E_E") (pintype "passive"))
      (node (ref "Ra3") (pin "2") (pinfunction "2_2") (pintype "passive"))
      (node (ref "Re1") (pin "2") (pinfunction "2_2") (pintype "passive"))
      (node (ref "Ro2") (pin "1") (pinfunction "1_1") (pintype "passive"))
      (node (ref "U1") (pin "9") (pinfunction "GND_9") (pintype "passive"))
      (node (ref "U2") (pin "2") (pinfunction "GND_2") (pintype "passive"))
      (node (ref "U3") (pin "3") (pinfunction "GND_3") (pintype "passive"))
      (node (ref "U3") (pin "7") (pinfunction "A0_7") (pintype "passive"))
      (node (ref "U3") (pin "8") (pinfunction "A1_8") (pintype "passive"))
      (node (ref "U4") (pin "1") (pinfunction "DOUT_1") (pintype "passive"))
      (node (ref "U4") (pin "4") (pinfunction "VPP_4") (pintype "passive"))
      (node (ref "U4") (pin "9") (pinfunction "GND_9") (pintype "passive"))
      (node (ref "U5") (pin "9") (pinfunction "PGND_9") (pintype "passive"))
      (node (ref "U6") (pin "1") (pinfunction "ADJ/GND_1") (pintype "passive"))
    )
    (net (code "37") (name "Net-(J_Battery-+)") (class "Default")
      (node (ref "Cf_bat1") (pin "1") (pinfunction "1_1") (pintype "passive"))
      (node (ref "J_Battery") (pin "1") (pinfunction "+_1") (pintype "passive"))
      (node (ref "PB1") (pin "2") (pinfunction "2_2") (pintype "passive"))
    )
    (net (code "38") (name "Net-(J_MICROUSB-DATA+)") (class "Default")
      (node (ref "J_MICROUSB") (pin "3") (pinfunction "DATA+_3") (pintype "passive"))
      (node (ref "Rf_in1") (pin "2") (pinfunction "2_2") (pintype "passive"))
    )
    (net (code "39") (name "Net-(J_MICROUSB-DATA-)") (class "Default")
      (node (ref "J_MICROUSB") (pin "2") (pinfunction "DATA-_2") (pintype "passive"))
      (node (ref "Rf_in1") (pin "1") (pinfunction "1_1") (pintype "passive"))
    )
    (net (code "40") (name "Net-(U5-SW)") (class "Default")
      (node (ref "L_Ind") (pin "2") (pinfunction "2_2") (pintype "passive"))
      (node (ref "U5") (pin "7") (pinfunction "SW_7") (pintype "passive"))
    )
    (net (code "41") (name "unconnected-(J_MICROUSB-ID-Pad4)") (class "Default")
      (node (ref "J_MICROUSB") (pin "4") (pinfunction "ID_4") (pintype "passive"))
    )
    (net (code "42") (name "unconnected-(PB1-Pad1)") (class "Default")
      (node (ref "PB1") (pin "1") (pinfunction "1_1") (pintype "passive"))
    )
    (net (code "43") (name "unconnected-(U4-INT_2-Pad6)") (class "Default")
      (node (ref "U4") (pin "6") (pinfunction "INT_2_6") (pintype "passive"))
    )
  )
)
